# Tiny817_Xplained_Pro_current_measurement.net
KiCad netlist of a schematic drawn in Altium Designer
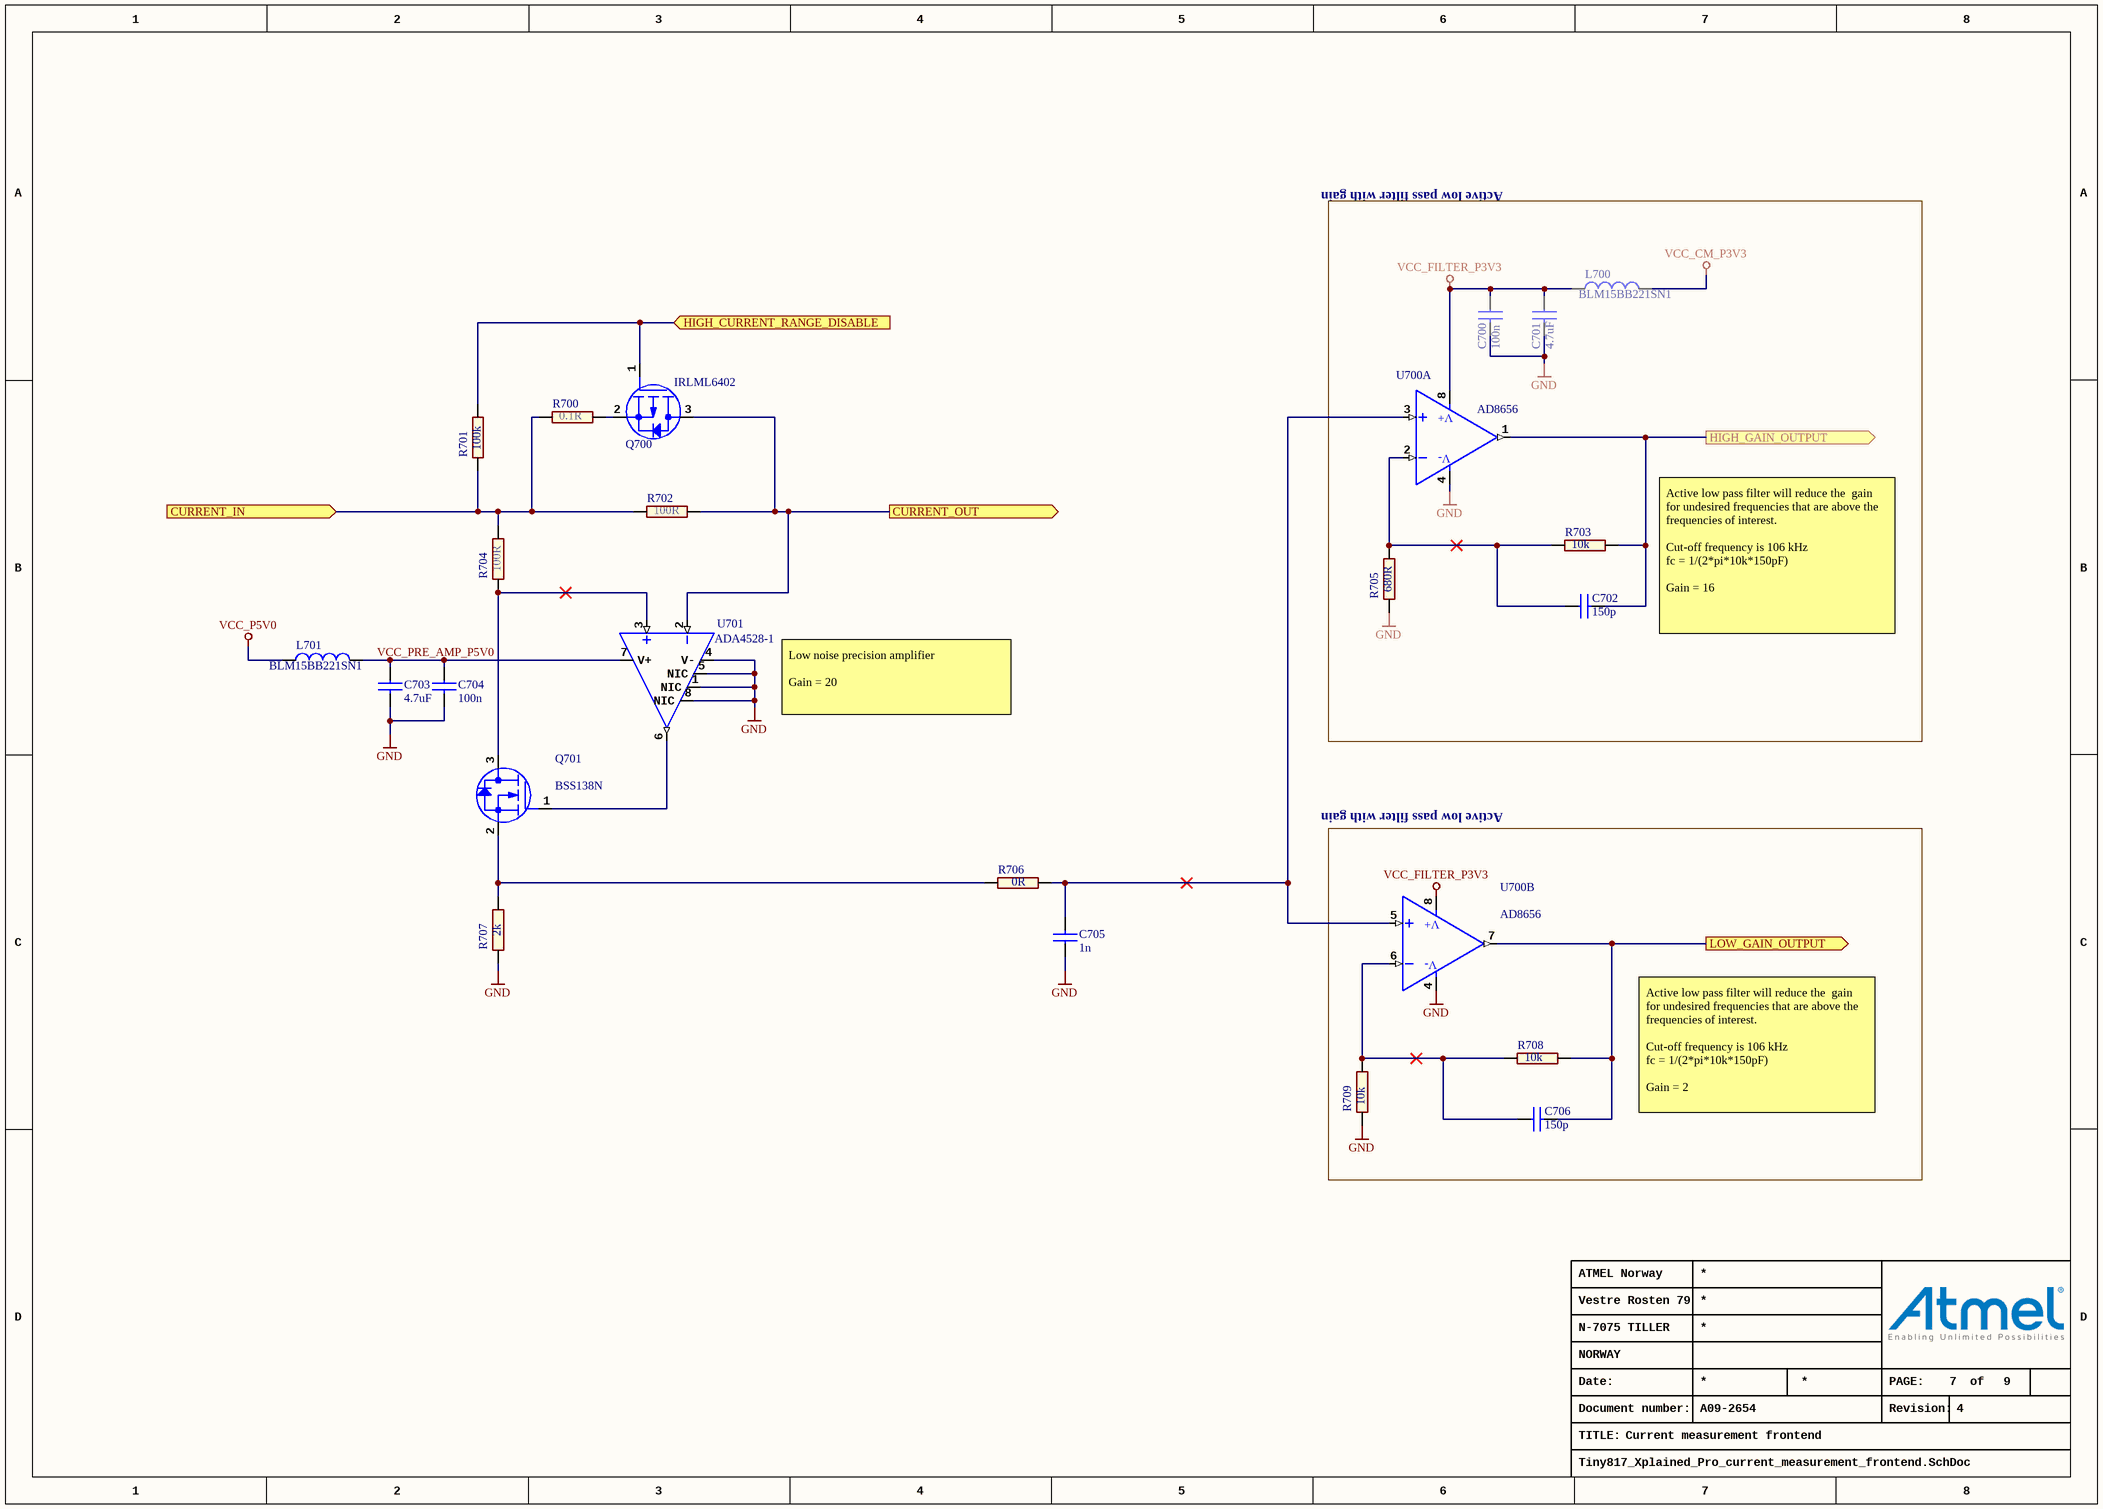
[diagram p0: Tiny817_Xplained_Pro_current_measurement_frontend.SchDoc]

(export (version "E")
  (design (tool "Eeschema 10.0.6"))
  (components
    (comp (ref "C700")
      (value "100n")
      (footprint "AP1-00053")
      (description "Ceramic capacitor, SMD 0402, X7R, 16V, +/-10%")
      (fields (field (name "TOLERANCE") "16V, +/-10%") (field (name "MANUFACTURER") "Kemet"))
      (libsource (lib "AltiumDbLib") (part "CAP-NONPOL"))
    )
    (comp (ref "C701")
      (value "4.7uF")
      (footprint "AP1-00117")
      (description "Ceramic capacitor, SMD 0603, X5R, 10V, 10% (de31036)")
      (fields (field (name "TOLERANCE") "10%") (field (name "MANUFACTURER") "WALSIN Technology Corporation"))
      (libsource (lib "AltiumDbLib") (part "CAP-NONPOL"))
    )
    (comp (ref "C702")
      (value "150p")
      (footprint "AP1-00053")
      (description "Ceramic capacitor, SMD 0402, X7R, 50V, +/-10%")
      (fields (field (name "TOLERANCE") "50V, +/-10%") (field (name "MANUFACTURER") "YAGEO CORP"))
      (libsource (lib "AltiumDbLib") (part "CAP-NONPOL"))
    )
    (comp (ref "C703")
      (value "4.7uF")
      (footprint "AP1-00117")
      (description "Ceramic capacitor, SMD 0603, X5R, 10V, 10% (de31036)")
      (fields (field (name "TOLERANCE") "10%") (field (name "MANUFACTURER") "WALSIN Technology Corporation"))
      (libsource (lib "AltiumDbLib") (part "CAP-NONPOL"))
    )
    (comp (ref "C704")
      (value "100n")
      (footprint "AP1-00053")
      (description "Ceramic capacitor, SMD 0402, X7R, 16V, +/-10%")
      (fields (field (name "TOLERANCE") "16V, +/-10%") (field (name "MANUFACTURER") "Kemet"))
      (libsource (lib "AltiumDbLib") (part "CAP-NONPOL"))
    )
    (comp (ref "C705")
      (value "1n")
      (footprint "AP1-00053")
      (description "Ceramic capacitor, SMD 0402, X7R, 50V, +/-10%")
      (fields (field (name "TOLERANCE") "50V, +/-10%") (field (name "MANUFACTURER") "YAGEO CORP"))
      (libsource (lib "AltiumDbLib") (part "CAP-NONPOL"))
    )
    (comp (ref "C706")
      (value "150p")
      (footprint "AP1-00053")
      (description "Ceramic capacitor, SMD 0402, X7R, 50V, +/-10%")
      (fields (field (name "TOLERANCE") "50V, +/-10%") (field (name "MANUFACTURER") "YAGEO CORP"))
      (libsource (lib "AltiumDbLib") (part "CAP-NONPOL"))
    )
    (comp (ref "L700")
      (value "BLM15BB221SN1")
      (footprint "AP3-00028")
      (description "SMD RF inductor 0402. Z=220Ohm (@100MHz), Max R(dc)=0.80Ohm, Max current=200mA")
      (fields (field (name "TOLERANCE") "±25%") (field (name "MANUFACTURER") "Murata"))
      (libsource (lib "AltiumDbLib") (part "INDUCTOR"))
    )
    (comp (ref "L701")
      (value "BLM15BB221SN1")
      (footprint "AP3-00028")
      (description "SMD RF inductor 0402. Z=220Ohm (@100MHz), Max R(dc)=0.80Ohm, Max current=200mA")
      (fields (field (name "TOLERANCE") "±25%") (field (name "MANUFACTURER") "Murata"))
      (libsource (lib "") (part "INDUCTOR_1"))
    )
    (comp (ref "Q700")
      (value "IRLML6402")
      (footprint "AP5-00002")
      (description "P-ch. MOSFET. -30V, -3.7A continuous,RDS(ON)=0.05Ohm@VGS=-4,5V, RDS(ON)=0.08Ohm@VGS=-2.5V")
      (fields (field (name "MANUFACTURER") "International Rectifier") (field (name "MPN") "IRLML6402PBF"))
      (libsource (lib "AltiumDbLib") (part "MOSFET_P_GSD"))
    )
    (comp (ref "Q701")
      (value "BSS138N")
      (footprint "AP5-00002")
      (fields (field (name "MANUFACTURER") "Infineon"))
      (libsource (lib "AltiumDbLib") (part "MOSFET_N_GSD"))
    )
    (comp (ref "R700")
      (value "0.1R")
      (footprint "AP2-00076")
      (description "WSL0603R1000FEA, metal strip resistor, 0.1 Ohm, +-1%, 0603 SMD, 1/10 W, TEMPCO +-75 ppm/Â°C")
      (fields (field (name "MANUFACTURER") "vishay") (field (name "MPN") "WSL0603R1000FEA"))
      (libsource (lib "") (part "R2_1"))
    )
    (comp (ref "R701")
      (value "100k")
      (footprint "AP2-00011")
      (description "Thick film resistor, SMD 0402, 1/16W, 1%")
      (fields (field (name "TOLERANCE") "1 %") (field (name "MANUFACTURER") "ASJ"))
      (libsource (lib "AltiumDbLib") (part "R2"))
    )
    (comp (ref "R702")
      (value "100R")
      (footprint "AP2-00076")
      (description "ERA-3YEB101V, metal film, 100R Â±0.1%, resistor in 0603 at 100mW, TEMPCO Â±25ppm/Â°C, Max V=75V")
      (fields (field (name "MANUFACTURER") "Panasonic") (field (name "MPN") "ERA3YEB101V"))
      (libsource (lib "") (part "R2_1"))
    )
    (comp (ref "R703")
      (value "10k")
      (footprint "AP2-00011")
      (description "Thick film resistor, SMD 0402, 1/16W, 1%")
      (fields (field (name "TOLERANCE") "1 %") (field (name "MANUFACTURER") "vishay"))
      (libsource (lib "") (part "R2_1"))
    )
    (comp (ref "R704")
      (value "100R")
      (footprint "AP2-00076")
      (description "ERA-3YEB101V, metal film, 100R Â±0.1%, resistor in 0603 at 100mW, TEMPCO Â±25ppm/Â°C, Max V=75V")
      (fields (field (name "MANUFACTURER") "Panasonic") (field (name "MPN") "ERA3YEB101V"))
      (libsource (lib "AltiumDbLib") (part "R2"))
    )
    (comp (ref "R705")
      (value "680R")
      (footprint "AP2-00011")
      (description "Thick film resistor, SMD 0402, 1/16W, 1%")
      (fields (field (name "TOLERANCE") "1 %") (field (name "MANUFACTURER") "ASJ"))
      (libsource (lib "AltiumDbLib") (part "R2"))
    )
    (comp (ref "R706")
      (value "0R")
      (footprint "AP2-00011")
      (description "RES 0.0 OHM 1/16W 0402 SMD")
      (fields (field (name "TOLERANCE") "1 %") (field (name "MANUFACTURER") "(n/a)"))
      (libsource (lib "") (part "R2_2"))
    )
    (comp (ref "R707")
      (value "2k")
      (footprint "AP2-00076")
      (description "Thick film resistor, SMD 0603, 1/10W, 1%")
      (fields (field (name "TOLERANCE") "1 %") (field (name "MANUFACTURER") "YAGEO CORP"))
      (libsource (lib "AltiumDbLib") (part "R2"))
    )
    (comp (ref "R708")
      (value "10k")
      (footprint "AP2-00011")
      (description "Thick film resistor, SMD 0402, 1/16W, 1%")
      (fields (field (name "TOLERANCE") "1 %") (field (name "MANUFACTURER") "vishay"))
      (libsource (lib "") (part "R2_1"))
    )
    (comp (ref "R709")
      (value "10k")
      (footprint "AP2-00011")
      (description "Thick film resistor, SMD 0402, 1/16W, 1%")
      (fields (field (name "TOLERANCE") "1 %") (field (name "MANUFACTURER") "vishay"))
      (libsource (lib "AltiumDbLib") (part "R2"))
    )
    (comp (ref "U700")
      (value "AD8656")
      (footprint "AP6-00100")
      (description "AD8656, dual low noise precision OpAmp, rail-to-rail, low offset 250uV, GBP 28 MHz, 8MSOP")
      (fields (field (name "MANUFACTURER") "Analog Devices") (field (name "MPN") "AD8656ARMZ"))
      (libsource (lib "AltiumDbLib") (part "AD8656"))
    )
    (comp (ref "U701")
      (value "ADA4528-1")
      (footprint "AP6-00100")
      (fields (field (name "MANUFACTURER") "Analog Devices") (field (name "MPN") "ADA4528-1ARMZ"))
      (libsource (lib "AltiumDbLib") (part "ADA4528-1"))
    )
  )
  (nets
    (net (code "1") (name "/CURRENT_IN") (class "Default")
      (node (ref "R700") (pin "1") (pinfunction "1_1") (pintype "passive"))
      (node (ref "R701") (pin "1") (pinfunction "1_1") (pintype "passive"))
      (node (ref "R702") (pin "1") (pinfunction "1_1") (pintype "passive"))
      (node (ref "R704") (pin "2") (pinfunction "2_2") (pintype "passive"))
    )
    (net (code "2") (name "/CURRENT_OUT") (class "Default")
      (node (ref "Q700") (pin "3") (pinfunction "D_3") (pintype "passive"))
      (node (ref "R702") (pin "2") (pinfunction "2_2") (pintype "passive"))
      (node (ref "U701") (pin "2") (pinfunction "IN-_2") (pintype "input"))
    )
    (net (code "3") (name "/HIGH_CURRENT_RANGE_DISABLE") (class "Default")
      (node (ref "Q700") (pin "1") (pinfunction "G_1") (pintype "passive"))
      (node (ref "R701") (pin "2") (pinfunction "2_2") (pintype "passive"))
    )
    (net (code "4") (name "/HIGH_GAIN_OUTPUT") (class "Default")
      (node (ref "C702") (pin "2") (pinfunction "2_2") (pintype "passive"))
      (node (ref "R703") (pin "2") (pinfunction "2_2") (pintype "passive"))
      (node (ref "U700") (pin "1") (pinfunction "OUTA_1") (pintype "output"))
    )
    (net (code "5") (name "/LOW_GAIN_OUTPUT") (class "Default")
      (node (ref "C706") (pin "2") (pinfunction "2_2") (pintype "passive"))
      (node (ref "R708") (pin "2") (pinfunction "2_2") (pintype "passive"))
      (node (ref "U700") (pin "7") (pinfunction "OUTB_7") (pintype "output"))
    )
    (net (code "6") (name "/VCC_PRE_AMP_P5V0") (class "Default")
      (node (ref "C703") (pin "1") (pinfunction "1_1") (pintype "passive"))
      (node (ref "C704") (pin "1") (pinfunction "1_1") (pintype "passive"))
      (node (ref "L701") (pin "2") (pinfunction "2_2") (pintype "passive"))
      (node (ref "U701") (pin "7") (pinfunction "V+_7") (pintype "power_in"))
    )
    (net (code "7") (name "GND") (class "Default")
      (node (ref "C700") (pin "2") (pinfunction "2_2") (pintype "passive"))
      (node (ref "C701") (pin "2") (pinfunction "2_2") (pintype "passive"))
      (node (ref "C703") (pin "2") (pinfunction "2_2") (pintype "passive"))
      (node (ref "C704") (pin "2") (pinfunction "2_2") (pintype "passive"))
      (node (ref "C705") (pin "1") (pinfunction "1_1") (pintype "passive"))
      (node (ref "R705") (pin "1") (pinfunction "1_1") (pintype "passive"))
      (node (ref "R707") (pin "1") (pinfunction "1_1") (pintype "passive"))
      (node (ref "R709") (pin "1") (pinfunction "1_1") (pintype "passive"))
      (node (ref "U700") (pin "4") (pinfunction "V-_4") (pintype "power_in"))
      (node (ref "U701") (pin "1") (pinfunction "NIC_1") (pintype "passive"))
      (node (ref "U701") (pin "4") (pinfunction "V-_4") (pintype "power_in"))
      (node (ref "U701") (pin "5") (pinfunction "NIC_5") (pintype "passive"))
      (node (ref "U701") (pin "8") (pinfunction "NIC_8") (pintype "passive"))
    )
    (net (code "8") (name "Net-(Q700-S)") (class "Default")
      (node (ref "Q700") (pin "2") (pinfunction "S_2") (pintype "passive"))
      (node (ref "R700") (pin "2") (pinfunction "2_2") (pintype "passive"))
    )
    (net (code "9") (name "Net-(Q701-D)") (class "Default")
      (node (ref "Q701") (pin "3") (pinfunction "D_3") (pintype "passive"))
      (node (ref "R704") (pin "1") (pinfunction "1_1") (pintype "passive"))
      (node (ref "U701") (pin "3") (pinfunction "IN+_3") (pintype "input"))
    )
    (net (code "10") (name "Net-(Q701-G)") (class "Default")
      (node (ref "Q701") (pin "1") (pinfunction "G_1") (pintype "passive"))
      (node (ref "U701") (pin "6") (pinfunction "OUT_6") (pintype "output"))
    )
    (net (code "11") (name "Net-(Q701-S)") (class "Default")
      (node (ref "Q701") (pin "2") (pinfunction "S_2") (pintype "passive"))
      (node (ref "R706") (pin "2") (pinfunction "2_2") (pintype "passive"))
      (node (ref "R707") (pin "2") (pinfunction "2_2") (pintype "passive"))
    )
    (net (code "12") (name "Net-(U700A-INA_+)") (class "Default")
      (node (ref "C705") (pin "2") (pinfunction "2_2") (pintype "passive"))
      (node (ref "R706") (pin "1") (pinfunction "1_1") (pintype "passive"))
      (node (ref "U700") (pin "3") (pinfunction "INA_+_3") (pintype "input"))
      (node (ref "U700") (pin "5") (pinfunction "INB_+_5") (pintype "input"))
    )
    (net (code "13") (name "Net-(U700A-INA_-)") (class "Default")
      (node (ref "C702") (pin "1") (pinfunction "1_1") (pintype "passive"))
      (node (ref "R703") (pin "1") (pinfunction "1_1") (pintype "passive"))
      (node (ref "R705") (pin "2") (pinfunction "2_2") (pintype "passive"))
      (node (ref "U700") (pin "2") (pinfunction "INA_-_2") (pintype "input"))
    )
    (net (code "14") (name "Net-(U700B-INB_-)") (class "Default")
      (node (ref "C706") (pin "1") (pinfunction "1_1") (pintype "passive"))
      (node (ref "R708") (pin "1") (pinfunction "1_1") (pintype "passive"))
      (node (ref "R709") (pin "2") (pinfunction "2_2") (pintype "passive"))
      (node (ref "U700") (pin "6") (pinfunction "INB_-_6") (pintype "input"))
    )
    (net (code "15") (name "VCC_CM_P3V3") (class "Default")
      (node (ref "L700") (pin "1") (pinfunction "1_1") (pintype "passive"))
    )
    (net (code "16") (name "VCC_FILTER_P3V3") (class "Default")
      (node (ref "C700") (pin "1") (pinfunction "1_1") (pintype "passive"))
      (node (ref "C701") (pin "1") (pinfunction "1_1") (pintype "passive"))
      (node (ref "L700") (pin "2") (pinfunction "2_2") (pintype "passive"))
      (node (ref "U700") (pin "8") (pinfunction "V+_8") (pintype "power_in"))
    )
    (net (code "17") (name "VCC_P5V0") (class "Default")
      (node (ref "L701") (pin "1") (pinfunction "1_1") (pintype "passive"))
    )
  )
)
